# pwr.net
KiCad netlist of a schematic drawn in EAGLE
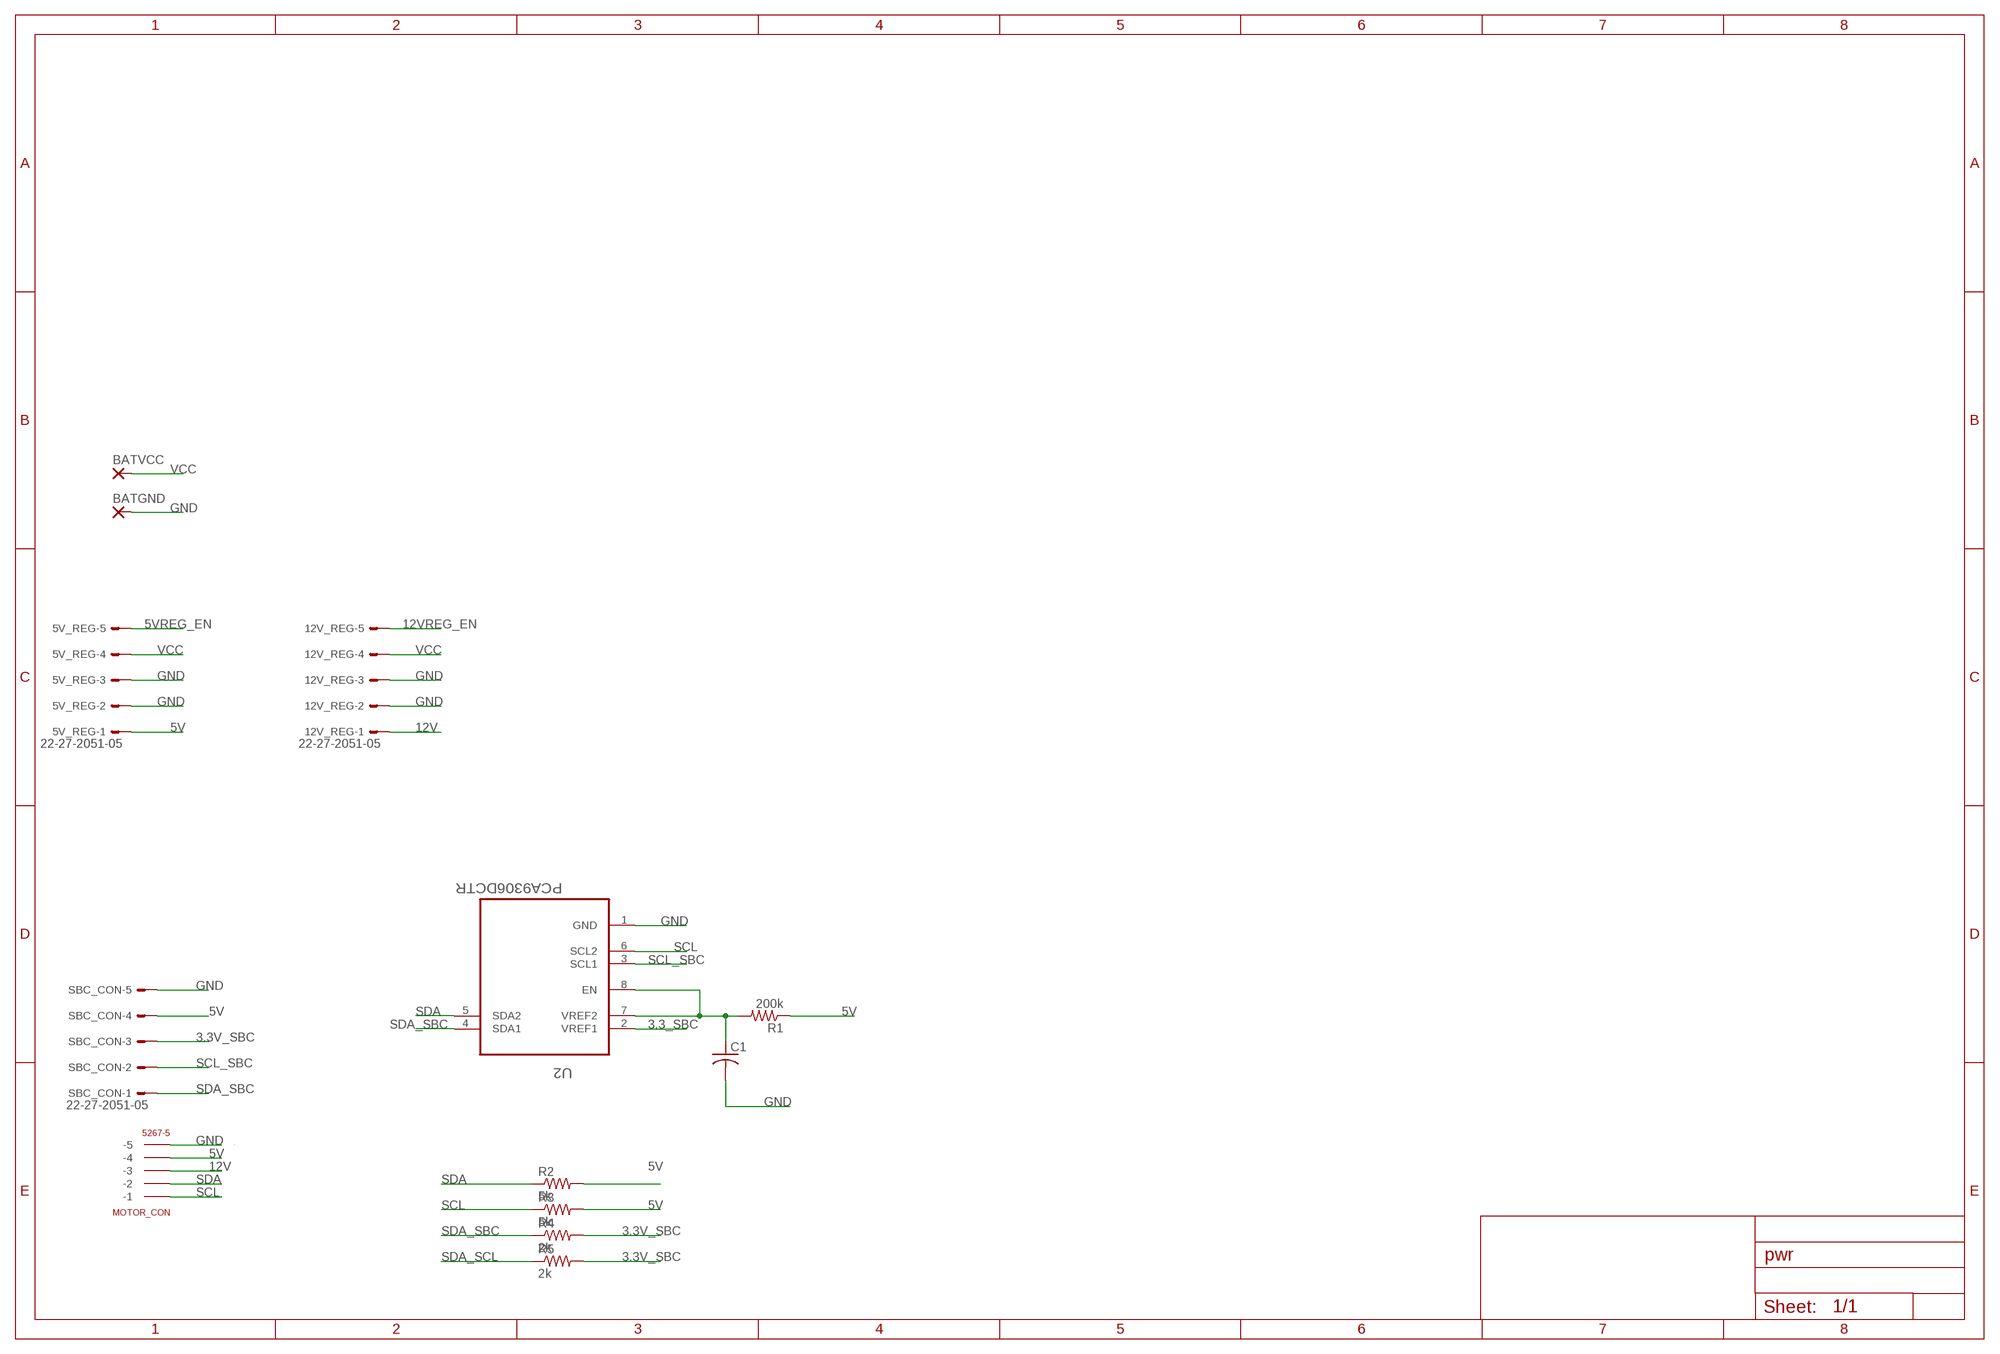
[diagram p0: schematic, sheet 1]

(export (version "E")
  (design (tool "Eeschema 10.0.6"))
  (components
    (comp (ref "5V_REG")
      (value "22-27-2051-05")
      (footprint "eagle-import:6410-05")
      (fields (field (name "MF") "MOLEX"))
      (libsource (lib "eagle-import") (part "22-?-0527-2051"))
    )
    (comp (ref "12V_REG")
      (value "22-27-2051-05")
      (footprint "eagle-import:6410-05")
      (fields (field (name "MF") "MOLEX"))
      (libsource (lib "eagle-import") (part "22-?-0527-2051"))
    )
    (comp (ref "BATGND")
      (value "SMD5")
      (footprint "eagle-import:SMD2,54-5,08")
      (libsource (lib "eagle-import") (part "SMD5"))
    )
    (comp (ref "BATVCC")
      (value "SMD5")
      (footprint "eagle-import:SMD2,54-5,08")
      (libsource (lib "eagle-import") (part "SMD5"))
    )
    (comp (ref "C1")
      (value "C-USC1210")
      (footprint "eagle-import:C1210")
      (libsource (lib "eagle-import") (part "C-USC1210"))
    )
    (comp (ref "MOTOR_CON")
      (value "5267-5")
      (footprint "eagle-import:5267-5")
      (libsource (lib "eagle-import") (part "5267-5"))
    )
    (comp (ref "R1")
      (value "200k")
      (footprint "eagle-import:R1210")
      (libsource (lib "eagle-import") (part "R-US_R1210"))
    )
    (comp (ref "R2")
      (value "5k")
      (footprint "eagle-import:R1210")
      (libsource (lib "eagle-import") (part "R-US_R1210"))
    )
    (comp (ref "R3")
      (value "5k")
      (footprint "eagle-import:R1210")
      (libsource (lib "eagle-import") (part "R-US_R1210"))
    )
    (comp (ref "R4")
      (value "2k")
      (footprint "eagle-import:R1210")
      (libsource (lib "eagle-import") (part "R-US_R1210"))
    )
    (comp (ref "R5")
      (value "2k")
      (footprint "eagle-import:R1210")
      (libsource (lib "eagle-import") (part "R-US_R1210"))
    )
    (comp (ref "SBC_CON")
      (value "22-27-2051-05")
      (footprint "eagle-import:6410-05")
      (fields (field (name "MF") "MOLEX"))
      (libsource (lib "eagle-import") (part "22-?-0527-2051"))
    )
    (comp (ref "U2")
      (value "PCA9306DCTR")
      (footprint "eagle-import:SOP65P400X130-8N")
      (libsource (lib "eagle-import") (part "PCA9306DCTR"))
    )
  )
  (nets
    (net (code "1") (name "/3.3V_SBC") (class "Default")
      (node (ref "R4") (pin "2") (pinfunction "2_2") (pintype "passive"))
      (node (ref "R5") (pin "2") (pinfunction "2_2") (pintype "passive"))
      (node (ref "SBC_CON") (pin "3") (pinfunction "S_3") (pintype "passive"))
    )
    (net (code "2") (name "/3.3_SBC") (class "Default")
      (node (ref "U2") (pin "2") (pinfunction "VREF1_2") (pintype "power_in"))
    )
    (net (code "3") (name "/5V") (class "Default")
      (node (ref "5V_REG") (pin "1") (pinfunction "S_1") (pintype "passive"))
      (node (ref "MOTOR_CON") (pin "P$4") (pinfunction "-4_P$4") (pintype "bidirectional"))
      (node (ref "R1") (pin "1") (pinfunction "1_1") (pintype "passive"))
      (node (ref "R2") (pin "2") (pinfunction "2_2") (pintype "passive"))
      (node (ref "R3") (pin "2") (pinfunction "2_2") (pintype "passive"))
      (node (ref "SBC_CON") (pin "4") (pinfunction "S_4") (pintype "passive"))
    )
    (net (code "4") (name "/5VREG_EN") (class "Default")
      (node (ref "5V_REG") (pin "5") (pinfunction "S_5") (pintype "passive"))
    )
    (net (code "5") (name "/12V") (class "Default")
      (node (ref "12V_REG") (pin "1") (pinfunction "S_1") (pintype "passive"))
      (node (ref "MOTOR_CON") (pin "P$3") (pinfunction "-3_P$3") (pintype "bidirectional"))
    )
    (net (code "6") (name "/12VREG_EN") (class "Default")
      (node (ref "12V_REG") (pin "5") (pinfunction "S_5") (pintype "passive"))
    )
    (net (code "7") (name "/GND") (class "Default")
      (node (ref "12V_REG") (pin "2") (pinfunction "S_2") (pintype "passive"))
      (node (ref "12V_REG") (pin "3") (pinfunction "S_3") (pintype "passive"))
      (node (ref "5V_REG") (pin "2") (pinfunction "S_2") (pintype "passive"))
      (node (ref "5V_REG") (pin "3") (pinfunction "S_3") (pintype "passive"))
      (node (ref "BATGND") (pin "1") (pinfunction "P_1") (pintype "passive"))
      (node (ref "C1") (pin "2") (pinfunction "2_2") (pintype "passive"))
      (node (ref "MOTOR_CON") (pin "P$5") (pinfunction "-5_P$5") (pintype "bidirectional"))
      (node (ref "SBC_CON") (pin "5") (pinfunction "S_5") (pintype "passive"))
      (node (ref "U2") (pin "1") (pinfunction "GND_1") (pintype "passive"))
    )
    (net (code "8") (name "/SCL") (class "Default")
      (node (ref "MOTOR_CON") (pin "P$1") (pinfunction "-1_P$1") (pintype "bidirectional"))
      (node (ref "R3") (pin "1") (pinfunction "1_1") (pintype "passive"))
      (node (ref "U2") (pin "6") (pinfunction "SCL2_6") (pintype "bidirectional"))
    )
    (net (code "9") (name "/SCL_SBC") (class "Default")
      (node (ref "SBC_CON") (pin "2") (pinfunction "S_2") (pintype "passive"))
      (node (ref "U2") (pin "3") (pinfunction "SCL1_3") (pintype "bidirectional"))
    )
    (net (code "10") (name "/SDA") (class "Default")
      (node (ref "MOTOR_CON") (pin "P$2") (pinfunction "-2_P$2") (pintype "bidirectional"))
      (node (ref "R2") (pin "1") (pinfunction "1_1") (pintype "passive"))
      (node (ref "U2") (pin "5") (pinfunction "SDA2_5") (pintype "bidirectional"))
    )
    (net (code "11") (name "/SDA_SBC") (class "Default")
      (node (ref "R4") (pin "1") (pinfunction "1_1") (pintype "passive"))
      (node (ref "SBC_CON") (pin "1") (pinfunction "S_1") (pintype "passive"))
      (node (ref "U2") (pin "4") (pinfunction "SDA1_4") (pintype "bidirectional"))
    )
    (net (code "12") (name "/SDA_SCL") (class "Default")
      (node (ref "R5") (pin "1") (pinfunction "1_1") (pintype "passive"))
    )
    (net (code "13") (name "/VCC") (class "Default")
      (node (ref "12V_REG") (pin "4") (pinfunction "S_4") (pintype "passive"))
      (node (ref "5V_REG") (pin "4") (pinfunction "S_4") (pintype "passive"))
      (node (ref "BATVCC") (pin "1") (pinfunction "P_1") (pintype "passive"))
    )
    (net (code "14") (name "Net-(U2-EN)") (class "Default")
      (node (ref "C1") (pin "1") (pinfunction "1_1") (pintype "passive"))
      (node (ref "R1") (pin "2") (pinfunction "2_2") (pintype "passive"))
      (node (ref "U2") (pin "7") (pinfunction "VREF2_7") (pintype "power_in"))
      (node (ref "U2") (pin "8") (pinfunction "EN_8") (pintype "input"))
    )
  )
)
